# WikiAudio.net
KiCad netlist of a schematic drawn in Altium Designer
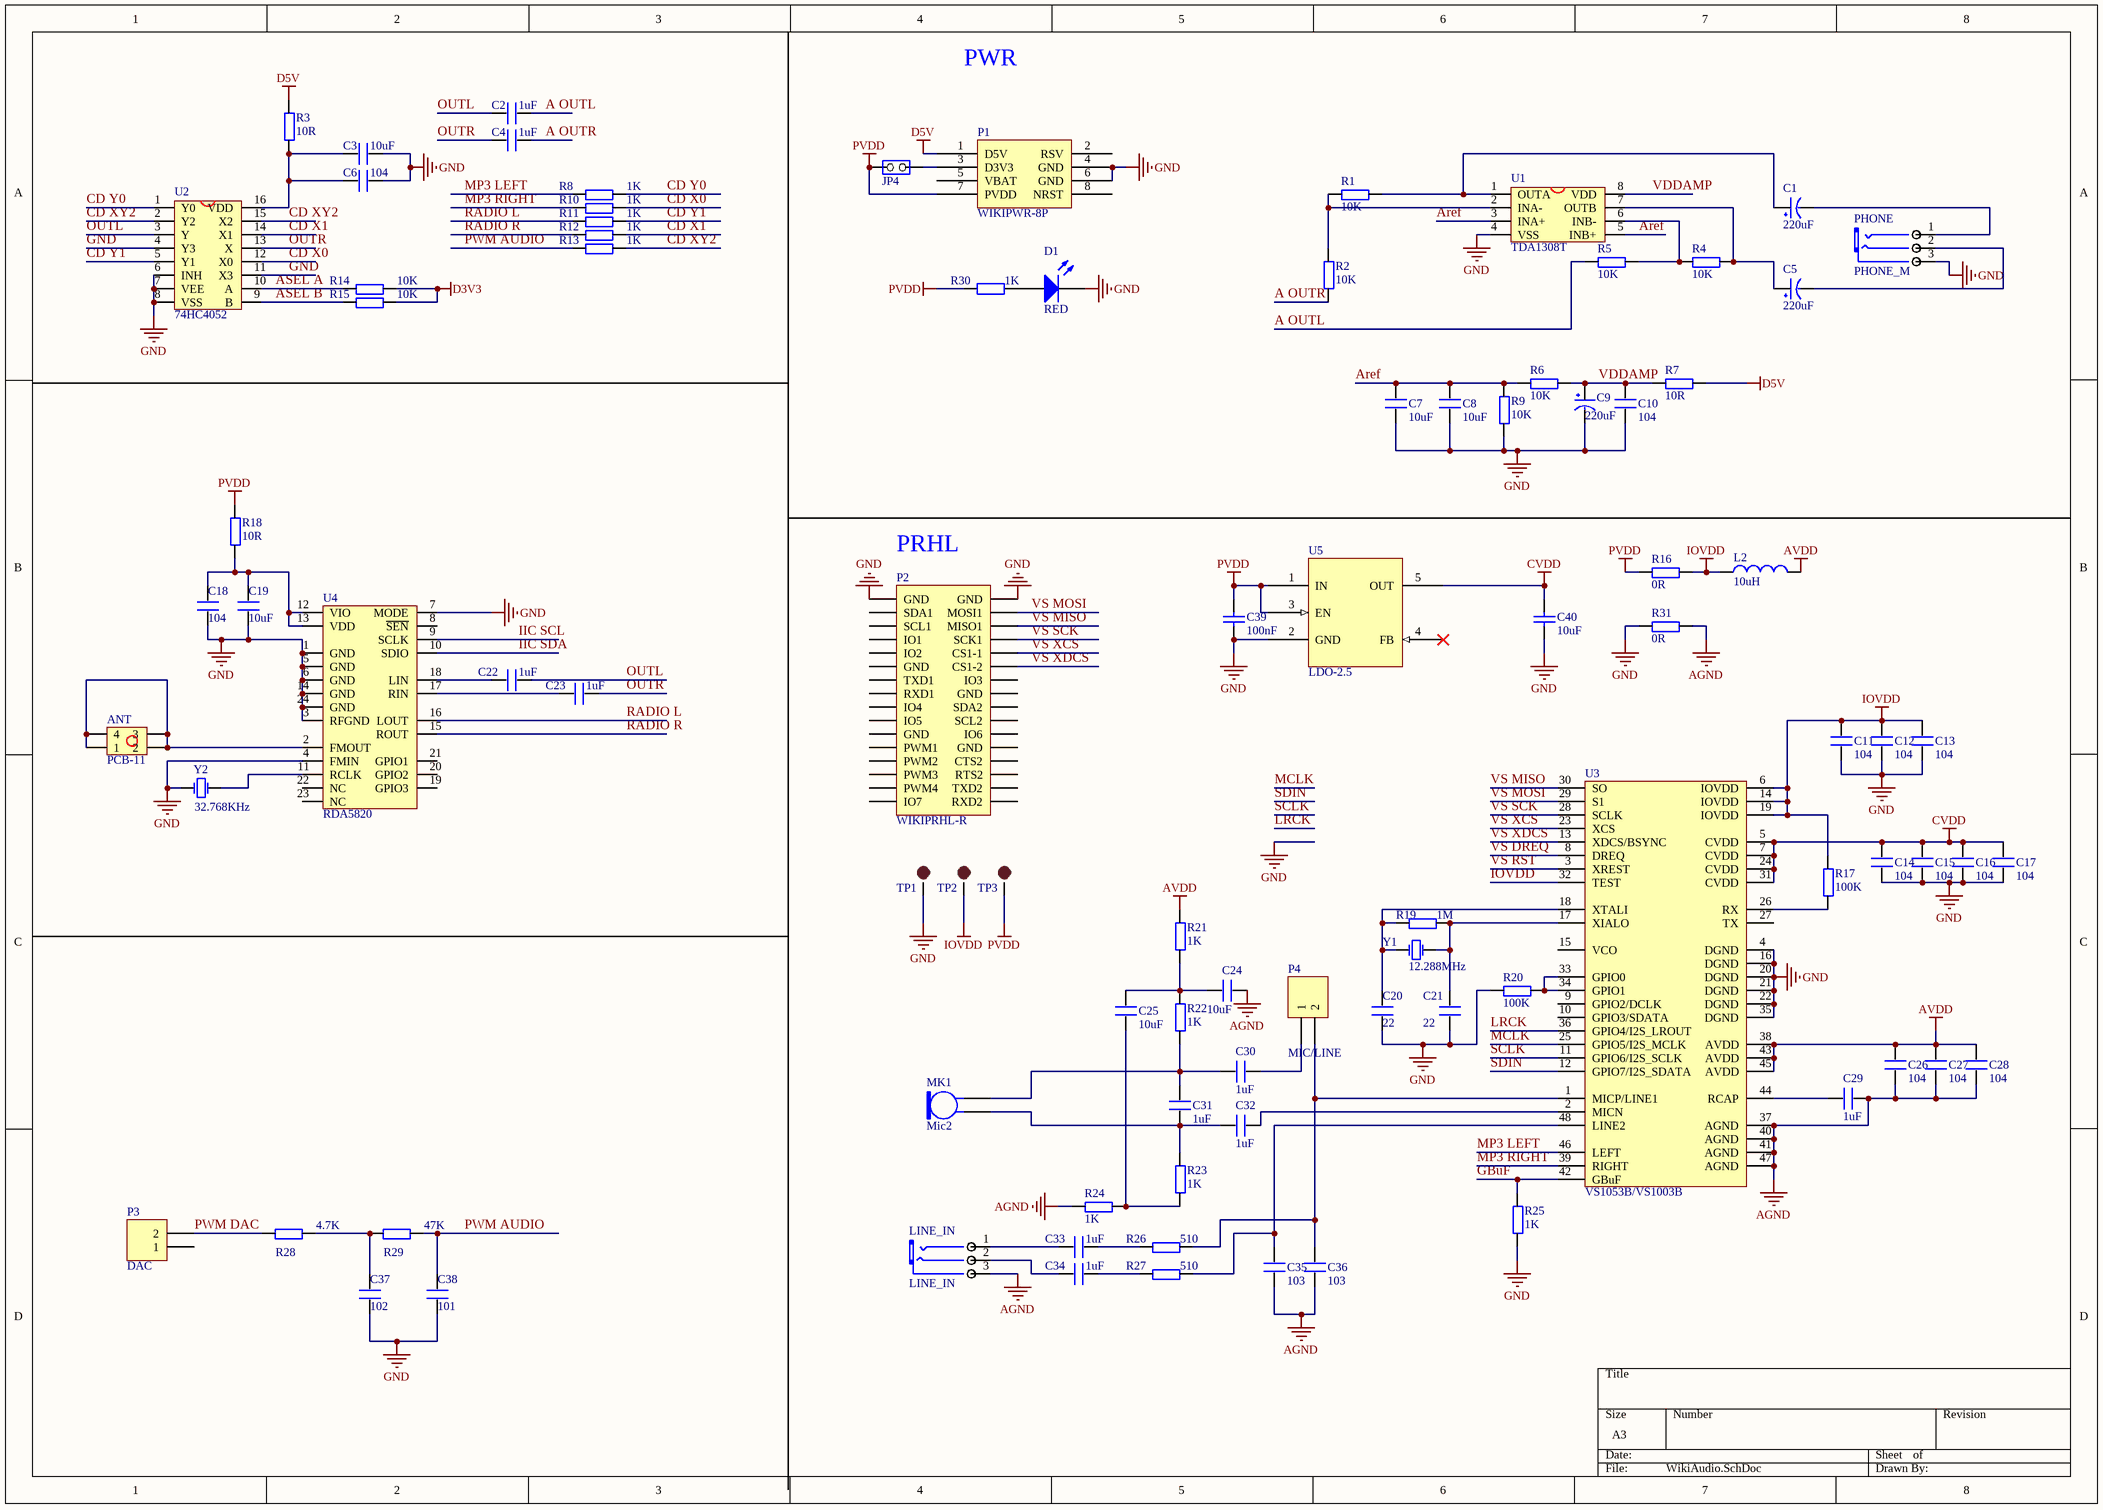
[diagram p0: WikiAudio.SchDoc]

(export (version "E")
  (design (tool "Eeschema 10.0.6"))
  (components
    (comp (ref "ANT")
      (value "PCB-11")
      (footprint "PCB-11")
      (description "PCB接线端子")
      (libsource (lib "战舰STM32开发板底板封装库") (part "PCB-11"))
    )
    (comp (ref "C1") (value "220uF") (footprint "CC6.56.5") (libsource (lib "战舰STM32开发板底板封装库") (part "CAP")))
    (comp (ref "C2") (value "1uF") (footprint "0603P") (libsource (lib "战舰STM32开发板底板封装库") (part "C")))
    (comp (ref "C3") (value "10uF") (footprint "0603P") (libsource (lib "战舰STM32开发板底板封装库") (part "C")))
    (comp (ref "C4") (value "1uF") (footprint "0603P") (libsource (lib "战舰STM32开发板底板封装库") (part "C")))
    (comp (ref "C5") (value "220uF") (footprint "CC6.56.5") (libsource (lib "战舰STM32开发板底板封装库") (part "CAP")))
    (comp (ref "C6") (value "104") (footprint "0603P") (libsource (lib "战舰STM32开发板底板封装库") (part "C")))
    (comp (ref "C7") (value "10uF") (footprint "0603P") (libsource (lib "战舰STM32开发板底板封装库") (part "C")))
    (comp (ref "C8") (value "10uF") (footprint "0603P") (libsource (lib "战舰STM32开发板底板封装库") (part "C")))
    (comp (ref "C9") (value "220uF") (footprint "CC6.56.5") (libsource (lib "") (part "CAP_1")))
    (comp (ref "C10") (value "104") (footprint "0603P") (libsource (lib "战舰STM32开发板底板封装库") (part "C")))
    (comp (ref "C11") (value "104") (footprint "0603P") (libsource (lib "战舰STM32开发板底板封装库") (part "C")))
    (comp (ref "C12") (value "104") (footprint "0603P") (libsource (lib "战舰STM32开发板底板封装库") (part "C")))
    (comp (ref "C13") (value "104") (footprint "0603P") (libsource (lib "战舰STM32开发板底板封装库") (part "C")))
    (comp (ref "C14") (value "104") (footprint "0603P") (libsource (lib "战舰STM32开发板底板封装库") (part "C")))
    (comp (ref "C15") (value "104") (footprint "0603P") (libsource (lib "战舰STM32开发板底板封装库") (part "C")))
    (comp (ref "C16") (value "104") (footprint "0603P") (libsource (lib "战舰STM32开发板底板封装库") (part "C")))
    (comp (ref "C17") (value "104") (footprint "0603P") (libsource (lib "战舰STM32开发板底板封装库") (part "C")))
    (comp (ref "C18") (value "104") (footprint "0603P") (libsource (lib "战舰STM32开发板底板封装库") (part "C")))
    (comp (ref "C19") (value "10uF") (footprint "0603P") (libsource (lib "战舰STM32开发板底板封装库") (part "C")))
    (comp (ref "C20") (value "22") (footprint "0603P") (libsource (lib "战舰STM32开发板底板封装库") (part "C")))
    (comp (ref "C21") (value "22") (footprint "0603P") (libsource (lib "战舰STM32开发板底板封装库") (part "C")))
    (comp (ref "C22") (value "1uF") (footprint "0603P") (libsource (lib "战舰STM32开发板底板封装库") (part "C")))
    (comp (ref "C23") (value "1uF") (footprint "0603P") (libsource (lib "战舰STM32开发板底板封装库") (part "C")))
    (comp (ref "C24") (value "10uF") (footprint "0603P") (libsource (lib "战舰STM32开发板底板封装库") (part "C")))
    (comp (ref "C25") (value "10uF") (footprint "0603P") (libsource (lib "战舰STM32开发板底板封装库") (part "C")))
    (comp (ref "C26") (value "104") (footprint "0603P") (libsource (lib "战舰STM32开发板底板封装库") (part "C")))
    (comp (ref "C27") (value "104") (footprint "0603P") (libsource (lib "战舰STM32开发板底板封装库") (part "C")))
    (comp (ref "C28") (value "104") (footprint "0603P") (libsource (lib "战舰STM32开发板底板封装库") (part "C")))
    (comp (ref "C29") (value "1uF") (footprint "0603P") (libsource (lib "战舰STM32开发板底板封装库") (part "C")))
    (comp (ref "C30") (value "1uF") (footprint "0603P") (libsource (lib "战舰STM32开发板底板封装库") (part "C")))
    (comp (ref "C31") (value "1uF") (footprint "0603P") (libsource (lib "战舰STM32开发板底板封装库") (part "C")))
    (comp (ref "C32") (value "1uF") (footprint "0603P") (libsource (lib "战舰STM32开发板底板封装库") (part "C")))
    (comp (ref "C33") (value "1uF") (footprint "0603P") (libsource (lib "战舰STM32开发板底板封装库") (part "C")))
    (comp (ref "C34") (value "1uF") (footprint "0603P") (libsource (lib "战舰STM32开发板底板封装库") (part "C")))
    (comp (ref "C35") (value "103") (footprint "0603P") (libsource (lib "战舰STM32开发板底板封装库") (part "C")))
    (comp (ref "C36") (value "103") (footprint "0603P") (libsource (lib "战舰STM32开发板底板封装库") (part "C")))
    (comp (ref "C37") (value "102") (footprint "0603P") (libsource (lib "战舰STM32开发板底板封装库") (part "C")))
    (comp (ref "C38") (value "101") (footprint "0603P") (libsource (lib "战舰STM32开发板底板封装库") (part "C")))
    (comp (ref "C39")
      (value "100nF")
      (footprint "C0603L")
      (description "Capacitor")
      (fields (field (name "PUBLISHER") "Altium Limited"))
      (libsource (lib "Miscellaneous Devices") (part "Cap"))
    )
    (comp (ref "C40")
      (value "10uF")
      (footprint "C0805")
      (description "Capacitor")
      (fields (field (name "PUBLISHER") "Altium Limited"))
      (libsource (lib "Miscellaneous Devices") (part "Cap"))
    )
    (comp (ref "D1")
      (value "RED")
      (footprint "0603pn")
      (description "Typical INFRARED GaAs LED")
      (fields (field (name "PUBLISHER") "Altium Limited"))
      (libsource (lib "Miscellaneous Devices") (part "LED0"))
    )
    (comp (ref "JP4")
      (value "Jumper2-2")
      (footprint "JP2_SMD")
      (description "Jumper2")
      (libsource (lib "Misc") (part "Jumper2-2"))
    )
    (comp (ref "L2")
      (value "10uH")
      (footprint "0805")
      (description "Inductor")
      (fields (field (name "PUBLISHER") "Altium Limited"))
      (libsource (lib "Misc") (part "Inductor"))
    )
    (comp (ref "LINE_IN")
      (value "LINE_IN")
      (footprint "PHONE_ST")
      (libsource (lib "战舰STM32开发板底板封装库") (part "PHONE_M"))
    )
    (comp (ref "MK1")
      (value "Mic2")
      (footprint "Mic-6050")
      (description "Microphone")
      (fields (field (name "PUBLISHER") "Altium Limited"))
      (libsource (lib "Misc") (part "Mic2"))
    )
    (comp (ref "P1")
      (value "WIKIPWR-8P")
      (footprint "WIKIPWR-8P")
      (description "PWR HDR")
      (libsource (lib "Connector") (part "WIKIPWR-8P"))
    )
    (comp (ref "P2")
      (value "WIKIPRHL-R")
      (footprint "WIKIPRHL-R")
      (description "Header, 16-Pin, Dual row")
      (fields (field (name "PUBLISHER") "Altium Limited"))
      (libsource (lib "Connector") (part "WIKIPRHL-R"))
    )
    (comp (ref "P3")
      (value "DAC")
      (footprint "HDR1X2")
      (description "Header, 2-Pin")
      (fields (field (name "PUBLISHER") "Altium Limited"))
      (libsource (lib "战舰STM32开发板底板封装库") (part "Header 2"))
    )
    (comp (ref "P4")
      (value "MIC/LINE")
      (footprint "HDR1X2/2.00MM")
      (description "Header, 2-Pin")
      (fields (field (name "PUBLISHER") "Altium Limited"))
      (libsource (lib "altium-import") (part "root_1_Header 2_"))
    )
    (comp (ref "PHONE")
      (value "PHONE_M")
      (footprint "PHONE_ST")
      (libsource (lib "战舰STM32开发板底板封装库") (part "PHONE_M"))
    )
    (comp (ref "R1") (value "10K") (footprint "0603P") (libsource (lib "战舰STM32开发板底板封装库") (part "R")))
    (comp (ref "R2") (value "10K") (footprint "0603P") (libsource (lib "战舰STM32开发板底板封装库") (part "R")))
    (comp (ref "R3") (value "10R") (footprint "0603P") (libsource (lib "战舰STM32开发板底板封装库") (part "R")))
    (comp (ref "R4") (value "10K") (footprint "0603P") (libsource (lib "战舰STM32开发板底板封装库") (part "R")))
    (comp (ref "R5") (value "10K") (footprint "0603P") (libsource (lib "战舰STM32开发板底板封装库") (part "R")))
    (comp (ref "R6") (value "10K") (footprint "0603P") (libsource (lib "战舰STM32开发板底板封装库") (part "R")))
    (comp (ref "R7") (value "10R") (footprint "0603P") (libsource (lib "战舰STM32开发板底板封装库") (part "R")))
    (comp (ref "R8") (value "1K") (footprint "0603P") (libsource (lib "战舰STM32开发板底板封装库") (part "R")))
    (comp (ref "R9") (value "10K") (footprint "0603P") (libsource (lib "战舰STM32开发板底板封装库") (part "R")))
    (comp (ref "R10") (value "1K") (footprint "0603P") (libsource (lib "战舰STM32开发板底板封装库") (part "R")))
    (comp (ref "R11") (value "1K") (footprint "0603P") (libsource (lib "战舰STM32开发板底板封装库") (part "R")))
    (comp (ref "R12") (value "1K") (footprint "0603P") (libsource (lib "战舰STM32开发板底板封装库") (part "R")))
    (comp (ref "R13") (value "1K") (footprint "0603P") (libsource (lib "战舰STM32开发板底板封装库") (part "R")))
    (comp (ref "R14") (value "10K") (footprint "0603P") (libsource (lib "战舰STM32开发板底板封装库") (part "R")))
    (comp (ref "R15") (value "10K") (footprint "0603P") (libsource (lib "战舰STM32开发板底板封装库") (part "R")))
    (comp (ref "R16")
      (value "0R")
      (footprint "0603P")
      (libsource (lib "altium-import") (part "root_0_mirrored_R_"))
    )
    (comp (ref "R17") (value "100K") (footprint "0603P") (libsource (lib "战舰STM32开发板底板封装库") (part "R")))
    (comp (ref "R18") (value "10R") (footprint "0603P") (libsource (lib "战舰STM32开发板底板封装库") (part "R")))
    (comp (ref "R19") (value "1M") (footprint "0603P") (libsource (lib "战舰STM32开发板底板封装库") (part "R")))
    (comp (ref "R20") (value "100K") (footprint "0603P") (libsource (lib "战舰STM32开发板底板封装库") (part "R")))
    (comp (ref "R21") (value "1K") (footprint "0603P") (libsource (lib "战舰STM32开发板底板封装库") (part "R")))
    (comp (ref "R22") (value "1K") (footprint "0603P") (libsource (lib "战舰STM32开发板底板封装库") (part "R")))
    (comp (ref "R23") (value "1K") (footprint "0603P") (libsource (lib "战舰STM32开发板底板封装库") (part "R")))
    (comp (ref "R24") (value "1K") (footprint "0603P") (libsource (lib "战舰STM32开发板底板封装库") (part "R")))
    (comp (ref "R25") (value "1K") (footprint "0603P") (libsource (lib "战舰STM32开发板底板封装库") (part "R")))
    (comp (ref "R26") (value "510") (footprint "0603P") (libsource (lib "战舰STM32开发板底板封装库") (part "R")))
    (comp (ref "R27") (value "510") (footprint "0603P") (libsource (lib "战舰STM32开发板底板封装库") (part "R")))
    (comp (ref "R28") (value "4.7K") (footprint "0603P") (libsource (lib "战舰STM32开发板底板封装库") (part "R")))
    (comp (ref "R29") (value "47K") (footprint "0603P") (libsource (lib "战舰STM32开发板底板封装库") (part "R")))
    (comp (ref "R30")
      (value "1K")
      (footprint "0603M")
      (description "Resistor")
      (fields (field (name "PUBLISHER") "Altium Limited"))
      (libsource (lib "Miscellaneous Devices") (part "Res2"))
    )
    (comp (ref "R31")
      (value "0R")
      (footprint "0603P")
      (libsource (lib "altium-import") (part "root_0_mirrored_R_"))
    )
    (comp (ref "TP1")
      (value "TEST POINT")
      (footprint "TP-1.5")
      (description "测试点")
      (libsource (lib "战舰STM32开发板底板封装库") (part "TEST-POINT"))
    )
    (comp (ref "TP2")
      (value "TEST POINT")
      (footprint "TP-1.5")
      (description "测试点")
      (libsource (lib "战舰STM32开发板底板封装库") (part "TEST-POINT"))
    )
    (comp (ref "TP3")
      (value "TEST POINT")
      (footprint "TP-1.5")
      (description "测试点")
      (libsource (lib "战舰STM32开发板底板封装库") (part "TEST-POINT"))
    )
    (comp (ref "U1")
      (value "TDA1308T")
      (footprint "SOP-8")
      (libsource (lib "战舰STM32开发板底板封装库") (part "TDA1308"))
    )
    (comp (ref "U2")
      (value "74HC4052")
      (footprint "SOP16M")
      (libsource (lib "战舰STM32开发板底板封装库") (part "CD4052"))
    )
    (comp (ref "U3")
      (value "VS1053B/VS1003B")
      (footprint "mTQFP48")
      (libsource (lib "altium-import") (part "root_0_VS1053_"))
    )
    (comp (ref "U4")
      (value "RDA5820")
      (footprint "QFN24")
      (libsource (lib "战舰STM32开发板底板封装库") (part "RDA5820"))
    )
    (comp (ref "U5")
      (value "LDO-2.5")
      (footprint "SOT23-5")
      (description "General LDO SOT23-5")
      (libsource (lib "Power") (part "LDO-SOT23-5"))
    )
    (comp (ref "Y1")
      (value "12.288MHz")
      (footprint "XTAL_US")
      (description "Crystal Oscillator")
      (fields (field (name "PUBLISHER") "Altium Limited"))
      (libsource (lib "战舰STM32开发板底板封装库") (part "XTAL_2"))
    )
    (comp (ref "Y2")
      (value "32.768KHz")
      (footprint "XTAL32")
      (description "32.768K")
      (fields (field (name "PUBLISHER") "Altium Limited"))
      (libsource (lib "战舰STM32开发板底板封装库") (part "XTAL_3"))
    )
  )
  (nets
    (net (code "1") (name "/A OUTL") (class "Default")
      (node (ref "C2") (pin "2") (pintype "passive"))
      (node (ref "R5") (pin "1") (pintype "passive"))
    )
    (net (code "2") (name "/A OUTR") (class "Default")
      (node (ref "C4") (pin "2") (pintype "passive"))
      (node (ref "R2") (pin "1") (pintype "passive"))
    )
    (net (code "3") (name "/ASEL A") (class "Default")
      (node (ref "R14") (pin "1") (pintype "passive"))
      (node (ref "U2") (pin "10") (pinfunction "A_10") (pintype "passive"))
    )
    (net (code "4") (name "/ASEL B") (class "Default")
      (node (ref "R15") (pin "1") (pintype "passive"))
      (node (ref "U2") (pin "9") (pinfunction "B_9") (pintype "passive"))
    )
    (net (code "5") (name "/Aref") (class "Default")
      (node (ref "C7") (pin "2") (pintype "passive"))
      (node (ref "C8") (pin "2") (pintype "passive"))
      (node (ref "R6") (pin "1") (pintype "passive"))
      (node (ref "R9") (pin "2") (pintype "passive"))
      (node (ref "U1") (pin "3") (pinfunction "INA+_3") (pintype "passive"))
      (node (ref "U1") (pin "5") (pinfunction "INB+_5") (pintype "passive"))
    )
    (net (code "6") (name "/CD X0") (class "Default")
      (node (ref "R10") (pin "2") (pintype "passive"))
      (node (ref "U2") (pin "12") (pinfunction "X0_12") (pintype "passive"))
    )
    (net (code "7") (name "/CD X1") (class "Default")
      (node (ref "R12") (pin "2") (pintype "passive"))
      (node (ref "U2") (pin "14") (pinfunction "X1_14") (pintype "passive"))
    )
    (net (code "8") (name "/CD XY2") (class "Default")
      (node (ref "R13") (pin "2") (pintype "passive"))
      (node (ref "U2") (pin "15") (pinfunction "X2_15") (pintype "passive"))
      (node (ref "U2") (pin "2") (pinfunction "Y2_2") (pintype "passive"))
    )
    (net (code "9") (name "/CD Y0") (class "Default")
      (node (ref "R8") (pin "2") (pintype "passive"))
      (node (ref "U2") (pin "1") (pinfunction "Y0_1") (pintype "passive"))
    )
    (net (code "10") (name "/CD Y1") (class "Default")
      (node (ref "R11") (pin "2") (pintype "passive"))
      (node (ref "U2") (pin "5") (pinfunction "Y1_5") (pintype "passive"))
    )
    (net (code "11") (name "/GBuF") (class "Default")
      (node (ref "R25") (pin "2") (pintype "passive"))
      (node (ref "U3") (pin "42") (pinfunction "GBuF_42") (pintype "passive"))
    )
    (net (code "12") (name "/IIC SCL") (class "Default")
      (node (ref "U4") (pin "9") (pinfunction "SCLK_9") (pintype "passive"))
    )
    (net (code "13") (name "/IIC SDA") (class "Default")
      (node (ref "U4") (pin "10") (pinfunction "SDIO_10") (pintype "passive"))
    )
    (net (code "14") (name "/LRCK") (class "Default")
      (node (ref "U3") (pin "36") (pinfunction "GPIO4/I2S_LROUT_36") (pintype "passive"))
    )
    (net (code "15") (name "/MCLK") (class "Default")
      (node (ref "U3") (pin "25") (pinfunction "GPIO5/I2S_MCLK_25") (pintype "passive"))
    )
    (net (code "16") (name "/MP3 LEFT") (class "Default")
      (node (ref "R8") (pin "1") (pintype "passive"))
      (node (ref "U3") (pin "46") (pinfunction "LEFT_46") (pintype "passive"))
    )
    (net (code "17") (name "/MP3 RIGHT") (class "Default")
      (node (ref "R10") (pin "1") (pintype "passive"))
      (node (ref "U3") (pin "39") (pinfunction "RIGHT_39") (pintype "passive"))
    )
    (net (code "18") (name "/OUTL") (class "Default")
      (node (ref "C2") (pin "1") (pintype "passive"))
      (node (ref "C22") (pin "1") (pintype "passive"))
      (node (ref "U2") (pin "3") (pinfunction "Y_3") (pintype "passive"))
    )
    (net (code "19") (name "/OUTR") (class "Default")
      (node (ref "C23") (pin "1") (pintype "passive"))
      (node (ref "C4") (pin "1") (pintype "passive"))
      (node (ref "U2") (pin "13") (pinfunction "X_13") (pintype "passive"))
    )
    (net (code "20") (name "/PWM AUDIO") (class "Default")
      (node (ref "C38") (pin "2") (pintype "passive"))
      (node (ref "R13") (pin "1") (pintype "passive"))
      (node (ref "R29") (pin "2") (pintype "passive"))
    )
    (net (code "21") (name "/PWM DAC") (class "Default")
      (node (ref "P3") (pin "2") (pinfunction "2_2") (pintype "passive"))
      (node (ref "R28") (pin "1") (pintype "passive"))
    )
    (net (code "22") (name "/RADIO L") (class "Default")
      (node (ref "R11") (pin "1") (pintype "passive"))
      (node (ref "U4") (pin "16") (pinfunction "LOUT_16") (pintype "passive"))
    )
    (net (code "23") (name "/RADIO R") (class "Default")
      (node (ref "R12") (pin "1") (pintype "passive"))
      (node (ref "U4") (pin "15") (pinfunction "ROUT_15") (pintype "passive"))
    )
    (net (code "24") (name "/SCLK") (class "Default")
      (node (ref "U3") (pin "11") (pinfunction "GPIO6/I2S_SCLK_11") (pintype "passive"))
    )
    (net (code "25") (name "/SDIN") (class "Default")
      (node (ref "U3") (pin "12") (pinfunction "GPIO7/I2S_SDATA_12") (pintype "passive"))
    )
    (net (code "26") (name "/VDDAMP") (class "Default")
      (node (ref "C10") (pin "2") (pintype "passive"))
      (node (ref "C9") (pin "1") (pinfunction "VCC_1") (pintype "passive"))
      (node (ref "R6") (pin "2") (pintype "passive"))
      (node (ref "R7") (pin "1") (pintype "passive"))
      (node (ref "U1") (pin "8") (pinfunction "VDD_8") (pintype "passive"))
    )
    (net (code "27") (name "/VS DREQ") (class "Default")
      (node (ref "U3") (pin "8") (pinfunction "DREQ_8") (pintype "passive"))
    )
    (net (code "28") (name "/VS MISO") (class "Default")
      (node (ref "P2") (pin "6") (pinfunction "MISO1_6") (pintype "passive"))
      (node (ref "U3") (pin "30") (pinfunction "SO_30") (pintype "passive"))
    )
    (net (code "29") (name "/VS MOSI") (class "Default")
      (node (ref "P2") (pin "4") (pinfunction "MOSI1_4") (pintype "passive"))
      (node (ref "U3") (pin "29") (pinfunction "S1_29") (pintype "passive"))
    )
    (net (code "30") (name "/VS RST") (class "Default")
      (node (ref "U3") (pin "3") (pinfunction "XREST_3") (pintype "passive"))
    )
    (net (code "31") (name "/VS SCK") (class "Default")
      (node (ref "P2") (pin "8") (pinfunction "SCK1_8") (pintype "passive"))
      (node (ref "U3") (pin "28") (pinfunction "SCLK_28") (pintype "passive"))
    )
    (net (code "32") (name "/VS XCS") (class "Default")
      (node (ref "P2") (pin "10") (pinfunction "CS1-1_10") (pintype "passive"))
      (node (ref "U3") (pin "23") (pinfunction "XCS_23") (pintype "passive"))
    )
    (net (code "33") (name "/VS XDCS") (class "Default")
      (node (ref "P2") (pin "12") (pinfunction "CS1-2_12") (pintype "passive"))
      (node (ref "U3") (pin "13") (pinfunction "XDCS/BSYNC_13") (pintype "passive"))
    )
    (net (code "34") (name "AGND") (class "Default")
      (node (ref "C24") (pin "1") (pintype "passive"))
      (node (ref "C26") (pin "1") (pintype "passive"))
      (node (ref "C27") (pin "1") (pintype "passive"))
      (node (ref "C28") (pin "1") (pintype "passive"))
      (node (ref "C29") (pin "2") (pintype "passive"))
      (node (ref "C35") (pin "1") (pintype "passive"))
      (node (ref "C36") (pin "1") (pintype "passive"))
      (node (ref "LINE_IN") (pin "3") (pinfunction "COM_3") (pintype "passive"))
      (node (ref "R24") (pin "1") (pintype "passive"))
      (node (ref "R31") (pin "1") (pintype "passive"))
      (node (ref "U3") (pin "37") (pinfunction "AGND_37") (pintype "passive"))
      (node (ref "U3") (pin "40") (pinfunction "AGND_40") (pintype "passive"))
      (node (ref "U3") (pin "41") (pinfunction "AGND_41") (pintype "passive"))
      (node (ref "U3") (pin "47") (pinfunction "AGND_47") (pintype "passive"))
    )
    (net (code "35") (name "AVDD") (class "Default")
      (node (ref "C26") (pin "2") (pintype "passive"))
      (node (ref "C27") (pin "2") (pintype "passive"))
      (node (ref "C28") (pin "2") (pintype "passive"))
      (node (ref "L2") (pin "2") (pinfunction "2_2") (pintype "passive"))
      (node (ref "R21") (pin "2") (pintype "passive"))
      (node (ref "U3") (pin "38") (pinfunction "AVDD_38") (pintype "passive"))
      (node (ref "U3") (pin "43") (pinfunction "AVDD_43") (pintype "passive"))
      (node (ref "U3") (pin "45") (pinfunction "AVDD_45") (pintype "passive"))
    )
    (net (code "36") (name "CVDD") (class "Default")
      (node (ref "C14") (pin "2") (pintype "passive"))
      (node (ref "C15") (pin "2") (pintype "passive"))
      (node (ref "C16") (pin "2") (pintype "passive"))
      (node (ref "C17") (pin "2") (pintype "passive"))
      (node (ref "C40") (pin "1") (pinfunction "1_1") (pintype "passive"))
      (node (ref "U3") (pin "24") (pinfunction "CVDD_24") (pintype "passive"))
      (node (ref "U3") (pin "31") (pinfunction "CVDD_31") (pintype "passive"))
      (node (ref "U3") (pin "5") (pinfunction "CVDD_5") (pintype "passive"))
      (node (ref "U3") (pin "7") (pinfunction "CVDD_7") (pintype "passive"))
      (node (ref "U5") (pin "5") (pinfunction "OUT_5") (pintype "power_in"))
    )
    (net (code "37") (name "D3V3") (class "Default")
      (node (ref "R14") (pin "2") (pintype "passive"))
      (node (ref "R15") (pin "2") (pintype "passive"))
    )
    (net (code "38") (name "D5V") (class "Default")
      (node (ref "P1") (pin "1") (pinfunction "D5V_1") (pintype "passive"))
      (node (ref "R3") (pin "2") (pintype "passive"))
      (node (ref "R7") (pin "2") (pintype "passive"))
    )
    (net (code "39") (name "GND") (class "Default")
      (node (ref "C10") (pin "1") (pintype "passive"))
      (node (ref "C11") (pin "1") (pintype "passive"))
      (node (ref "C12") (pin "1") (pintype "passive"))
      (node (ref "C13") (pin "1") (pintype "passive"))
      (node (ref "C14") (pin "1") (pintype "passive"))
      (node (ref "C15") (pin "1") (pintype "passive"))
      (node (ref "C16") (pin "1") (pintype "passive"))
      (node (ref "C17") (pin "1") (pintype "passive"))
      (node (ref "C18") (pin "1") (pintype "passive"))
      (node (ref "C19") (pin "1") (pintype "passive"))
      (node (ref "C20") (pin "1") (pintype "passive"))
      (node (ref "C21") (pin "1") (pintype "passive"))
      (node (ref "C3") (pin "2") (pintype "passive"))
      (node (ref "C37") (pin "1") (pintype "passive"))
      (node (ref "C38") (pin "1") (pintype "passive"))
      (node (ref "C39") (pin "2") (pinfunction "2_2") (pintype "passive"))
      (node (ref "C40") (pin "2") (pinfunction "2_2") (pintype "passive"))
      (node (ref "C6") (pin "2") (pintype "passive"))
      (node (ref "C7") (pin "1") (pintype "passive"))
      (node (ref "C8") (pin "1") (pintype "passive"))
      (node (ref "C9") (pin "2") (pinfunction "GND_2") (pintype "passive"))
      (node (ref "D1") (pin "2") (pinfunction "K_2") (pintype "passive"))
      (node (ref "P1") (pin "4") (pinfunction "GND_4") (pintype "passive"))
      (node (ref "P1") (pin "6") (pinfunction "GND_6") (pintype "passive"))
      (node (ref "P2") (pin "1") (pinfunction "GND_1") (pintype "passive"))
      (node (ref "P2") (pin "2") (pinfunction "GND_2") (pintype "passive"))
      (node (ref "PHONE") (pin "3") (pinfunction "COM_3") (pintype "passive"))
      (node (ref "R20") (pin "1") (pintype "passive"))
      (node (ref "R25") (pin "1") (pintype "passive"))
      (node (ref "R31") (pin "2") (pintype "passive"))
      (node (ref "R9") (pin "1") (pintype "passive"))
      (node (ref "TP1") (pin "1") (pinfunction "1_1") (pintype "passive"))
      (node (ref "U1") (pin "4") (pinfunction "VSS_4") (pintype "passive"))
      (node (ref "U2") (pin "11") (pinfunction "X3_11") (pintype "passive"))
      (node (ref "U2") (pin "4") (pinfunction "Y3_4") (pintype "passive"))
      (node (ref "U2") (pin "6") (pinfunction "INH_6") (pintype "passive"))
      (node (ref "U2") (pin "7") (pinfunction "VEE_7") (pintype "passive"))
      (node (ref "U2") (pin "8") (pinfunction "VSS_8") (pintype "passive"))
      (node (ref "U3") (pin "16") (pinfunction "DGND_16") (pintype "passive"))
      (node (ref "U3") (pin "20") (pinfunction "DGND_20") (pintype "passive"))
      (node (ref "U3") (pin "21") (pinfunction "DGND_21") (pintype "passive"))
      (node (ref "U3") (pin "22") (pinfunction "DGND_22") (pintype "passive"))
      (node (ref "U3") (pin "35") (pinfunction "DGND_35") (pintype "passive"))
      (node (ref "U3") (pin "4") (pinfunction "DGND_4") (pintype "passive"))
      (node (ref "U4") (pin "1") (pinfunction "GND_1") (pintype "passive"))
      (node (ref "U4") (pin "14") (pinfunction "GND_14") (pintype "passive"))
      (node (ref "U4") (pin "24") (pinfunction "GND_24") (pintype "passive"))
      (node (ref "U4") (pin "3") (pinfunction "RFGND_3") (pintype "passive"))
      (node (ref "U4") (pin "4") (pinfunction "FMIN_4") (pintype "passive"))
      (node (ref "U4") (pin "5") (pinfunction "GND_5") (pintype "passive"))
      (node (ref "U4") (pin "6") (pinfunction "GND_6") (pintype "passive"))
      (node (ref "U4") (pin "7") (pinfunction "MODE_7") (pintype "passive"))
      (node (ref "U5") (pin "2") (pinfunction "GND_2") (pintype "power_in"))
      (node (ref "Y2") (pin "1") (pinfunction "OSC1_1") (pintype "passive"))
    )
    (net (code "40") (name "IOVDD") (class "Default")
      (node (ref "C11") (pin "2") (pintype "passive"))
      (node (ref "C12") (pin "2") (pintype "passive"))
      (node (ref "C13") (pin "2") (pintype "passive"))
      (node (ref "L2") (pin "1") (pinfunction "1_1") (pintype "passive"))
      (node (ref "R16") (pin "1") (pintype "passive"))
      (node (ref "R17") (pin "2") (pintype "passive"))
      (node (ref "TP2") (pin "1") (pinfunction "1_1") (pintype "passive"))
      (node (ref "U3") (pin "14") (pinfunction "IOVDD_14") (pintype "passive"))
      (node (ref "U3") (pin "19") (pinfunction "IOVDD_19") (pintype "passive"))
      (node (ref "U3") (pin "32") (pinfunction "TEST_32") (pintype "passive"))
      (node (ref "U3") (pin "6") (pinfunction "IOVDD_6") (pintype "passive"))
    )
    (net (code "41") (name "Net-(C1-GND)") (class "Default")
      (node (ref "C1") (pin "2") (pinfunction "GND_2") (pintype "passive"))
      (node (ref "PHONE") (pin "1") (pinfunction "CHL_1") (pintype "passive"))
    )
    (net (code "42") (name "Net-(C1-VCC)") (class "Default")
      (node (ref "C1") (pin "1") (pinfunction "VCC_1") (pintype "passive"))
      (node (ref "R1") (pin "2") (pintype "passive"))
      (node (ref "U1") (pin "1") (pinfunction "OUTA_1") (pintype "passive"))
    )
    (net (code "43") (name "Net-(C5-GND)") (class "Default")
      (node (ref "C5") (pin "2") (pinfunction "GND_2") (pintype "passive"))
      (node (ref "PHONE") (pin "2") (pinfunction "CHR_2") (pintype "passive"))
    )
    (net (code "44") (name "Net-(C5-VCC)") (class "Default")
      (node (ref "C5") (pin "1") (pinfunction "VCC_1") (pintype "passive"))
      (node (ref "R4") (pin "2") (pintype "passive"))
      (node (ref "U1") (pin "7") (pinfunction "OUTB_7") (pintype "passive"))
    )
    (net (code "45") (name "Net-(C24-Pad2)") (class "Default")
      (node (ref "C24") (pin "2") (pintype "passive"))
      (node (ref "C25") (pin "2") (pintype "passive"))
      (node (ref "R21") (pin "1") (pintype "passive"))
      (node (ref "R22") (pin "2") (pintype "passive"))
    )
    (net (code "46") (name "Net-(C25-Pad1)") (class "Default")
      (node (ref "C25") (pin "1") (pintype "passive"))
      (node (ref "R23") (pin "1") (pintype "passive"))
      (node (ref "R24") (pin "2") (pintype "passive"))
    )
    (net (code "47") (name "Net-(C30-Pad1)") (class "Default")
      (node (ref "C30") (pin "1") (pintype "passive"))
      (node (ref "C31") (pin "2") (pintype "passive"))
      (node (ref "MK1") (pin "2") (pinfunction "2_2") (pintype "passive"))
      (node (ref "R22") (pin "1") (pintype "passive"))
    )
    (net (code "48") (name "Net-(C30-Pad2)") (class "Default")
      (node (ref "C30") (pin "2") (pintype "passive"))
      (node (ref "P4") (pin "1") (pinfunction "1_1") (pintype "passive"))
    )
    (net (code "49") (name "Net-(C31-Pad1)") (class "Default")
      (node (ref "C31") (pin "1") (pintype "passive"))
      (node (ref "C32") (pin "1") (pintype "passive"))
      (node (ref "MK1") (pin "1") (pinfunction "1_1") (pintype "passive"))
      (node (ref "R23") (pin "2") (pintype "passive"))
    )
    (net (code "50") (name "Net-(C33-Pad2)") (class "Default")
      (node (ref "C33") (pin "2") (pintype "passive"))
      (node (ref "R26") (pin "1") (pintype "passive"))
    )
    (net (code "51") (name "Net-(C34-Pad2)") (class "Default")
      (node (ref "C34") (pin "2") (pintype "passive"))
      (node (ref "R27") (pin "1") (pintype "passive"))
    )
    (net (code "52") (name "Net-(C37-Pad2)") (class "Default")
      (node (ref "C37") (pin "2") (pintype "passive"))
      (node (ref "R28") (pin "2") (pintype "passive"))
      (node (ref "R29") (pin "1") (pintype "passive"))
    )
    (net (code "53") (name "Net-(D1-A)") (class "Default")
      (node (ref "D1") (pin "1") (pinfunction "A_1") (pintype "passive"))
      (node (ref "R30") (pin "1") (pinfunction "1_1") (pintype "passive"))
    )
    (net (code "54") (name "Net-(JP4-COMMON)") (class "Default")
      (node (ref "JP4") (pin "1") (pinfunction "COMMON_1") (pintype "passive"))
      (node (ref "P1") (pin "3") (pinfunction "D3V3_3") (pintype "passive"))
    )
    (net (code "55") (name "Net-(LINE_IN-CHL)") (class "Default")
      (node (ref "C33") (pin "1") (pintype "passive"))
      (node (ref "LINE_IN") (pin "1") (pinfunction "CHL_1") (pintype "passive"))
    )
    (net (code "56") (name "Net-(LINE_IN-CHR)") (class "Default")
      (node (ref "C34") (pin "1") (pintype "passive"))
      (node (ref "LINE_IN") (pin "2") (pinfunction "CHR_2") (pintype "passive"))
    )
    (net (code "57") (name "Net-(U1-INA-)") (class "Default")
      (node (ref "R1") (pin "1") (pintype "passive"))
      (node (ref "R2") (pin "2") (pintype "passive"))
      (node (ref "U1") (pin "2") (pinfunction "INA-_2") (pintype "passive"))
    )
    (net (code "58") (name "Net-(U1-INB-)") (class "Default")
      (node (ref "R4") (pin "1") (pintype "passive"))
      (node (ref "R5") (pin "2") (pintype "passive"))
      (node (ref "U1") (pin "6") (pinfunction "INB-_6") (pintype "passive"))
    )
    (net (code "59") (name "Net-(U2-VDD)") (class "Default")
      (node (ref "C3") (pin "1") (pintype "passive"))
      (node (ref "C6") (pin "1") (pintype "passive"))
      (node (ref "R3") (pin "1") (pintype "passive"))
      (node (ref "U2") (pin "16") (pinfunction "VDD_16") (pintype "passive"))
    )
    (net (code "60") (name "Net-(U3-GPIO0)") (class "Default")
      (node (ref "R20") (pin "2") (pintype "passive"))
      (node (ref "U3") (pin "33") (pinfunction "GPIO0_33") (pintype "passive"))
      (node (ref "U3") (pin "34") (pinfunction "GPIO1_34") (pintype "passive"))
    )
    (net (code "61") (name "Net-(U3-LINE2)") (class "Default")
      (node (ref "C35") (pin "2") (pintype "passive"))
      (node (ref "R27") (pin "2") (pintype "passive"))
      (node (ref "U3") (pin "48") (pinfunction "LINE2_48") (pintype "passive"))
    )
    (net (code "62") (name "Net-(U3-MICN)") (class "Default")
      (node (ref "C32") (pin "2") (pintype "passive"))
      (node (ref "U3") (pin "2") (pinfunction "MICN_2") (pintype "passive"))
    )
    (net (code "63") (name "Net-(U3-MICP{slash}LINE1)") (class "Default")
      (node (ref "C36") (pin "2") (pintype "passive"))
      (node (ref "P4") (pin "2") (pinfunction "2_2") (pintype "passive"))
      (node (ref "R26") (pin "2") (pintype "passive"))
      (node (ref "U3") (pin "1") (pinfunction "MICP/LINE1_1") (pintype "passive"))
    )
    (net (code "64") (name "Net-(U3-RCAP)") (class "Default")
      (node (ref "C29") (pin "1") (pintype "passive"))
      (node (ref "U3") (pin "44") (pinfunction "RCAP_44") (pintype "passive"))
    )
    (net (code "65") (name "Net-(U3-RX)") (class "Default")
      (node (ref "R17") (pin "1") (pintype "passive"))
      (node (ref "U3") (pin "26") (pinfunction "RX_26") (pintype "passive"))
    )
    (net (code "66") (name "Net-(U3-XIALO)") (class "Default")
      (node (ref "C21") (pin "2") (pintype "passive"))
      (node (ref "R19") (pin "2") (pintype "passive"))
      (node (ref "U3") (pin "17") (pinfunction "XIALO_17") (pintype "passive"))
      (node (ref "Y1") (pin "2") (pinfunction "OSC2_2") (pintype "passive"))
    )
    (net (code "67") (name "Net-(U3-XTALI)") (class "Default")
      (node (ref "C20") (pin "2") (pintype "passive"))
      (node (ref "R19") (pin "1") (pintype "passive"))
      (node (ref "U3") (pin "18") (pinfunction "XTALI_18") (pintype "passive"))
      (node (ref "Y1") (pin "1") (pinfunction "OSC1_1") (pintype "passive"))
    )
    (net (code "68") (name "Net-(U4-FMOUT)") (class "Default")
      (node (ref "ANT") (pin "1") (pinfunction "1_1") (pintype "passive"))
      (node (ref "ANT") (pin "2") (pinfunction "2_2") (pintype "passive"))
      (node (ref "ANT") (pin "3") (pinfunction "3_3") (pintype "passive"))
      (node (ref "ANT") (pin "4") (pinfunction "4_4") (pintype "passive"))
      (node (ref "U4") (pin "2") (pinfunction "FMOUT_2") (pintype "passive"))
    )
    (net (code "69") (name "Net-(U4-LIN)") (class "Default")
      (node (ref "C22") (pin "2") (pintype "passive"))
      (node (ref "U4") (pin "18") (pinfunction "LIN_18") (pintype "passive"))
    )
    (net (code "70") (name "Net-(U4-RCLK)") (class "Default")
      (node (ref "U4") (pin "11") (pinfunction "RCLK_11") (pintype "passive"))
      (node (ref "Y2") (pin "2") (pinfunction "OSC2_2") (pintype "passive"))
    )
    (net (code "71") (name "Net-(U4-RIN)") (class "Default")
      (node (ref "C23") (pin "2") (pintype "passive"))
      (node (ref "U4") (pin "17") (pinfunction "RIN_17") (pintype "passive"))
    )
    (net (code "72") (name "Net-(U4-VDD)") (class "Default")
      (node (ref "C18") (pin "2") (pintype "passive"))
      (node (ref "C19") (pin "2") (pintype "passive"))
      (node (ref "R18") (pin "1") (pintype "passive"))
      (node (ref "U4") (pin "12") (pinfunction "VIO_12") (pintype "passive"))
      (node (ref "U4") (pin "13") (pinfunction "VDD_13") (pintype "passive"))
    )
    (net (code "73") (name "PVDD") (class "Default")
      (node (ref "C39") (pin "1") (pinfunction "1_1") (pintype "passive"))
      (node (ref "JP4") (pin "2") (pinfunction "NO_2") (pintype "passive"))
      (node (ref "P1") (pin "7") (pinfunction "PVDD_7") (pintype "passive"))
      (node (ref "R16") (pin "2") (pintype "passive"))
      (node (ref "R18") (pin "2") (pintype "passive"))
      (node (ref "R30") (pin "2") (pinfunction "2_2") (pintype "passive"))
      (node (ref "TP3") (pin "1") (pinfunction "1_1") (pintype "passive"))
      (node (ref "U5") (pin "1") (pinfunction "IN_1") (pintype "power_in"))
      (node (ref "U5") (pin "3") (pinfunction "EN_3") (pintype "input"))
    )
    (net (code "74") (name "unconnected-(P1-NRST-Pad8)") (class "Default")
      (node (ref "P1") (pin "8") (pinfunction "NRST_8") (pintype "passive"))
    )
    (net (code "75") (name "unconnected-(P1-RSV-Pad2)") (class "Default")
      (node (ref "P1") (pin "2") (pinfunction "RSV_2") (pintype "passive"))
    )
    (net (code "76") (name "unconnected-(P1-VBAT-Pad5)") (class "Default")
      (node (ref "P1") (pin "5") (pinfunction "VBAT_5") (pintype "passive"))
    )
    (net (code "77") (name "unconnected-(P2-CTS2-Pad26)") (class "Default")
      (node (ref "P2") (pin "26") (pinfunction "CTS2_26") (pintype "passive"))
    )
    (net (code "78") (name "unconnected-(P2-GND-Pad11)") (class "Default")
      (node (ref "P2") (pin "11") (pinfunction "GND_11") (pintype "passive"))
    )
    (net (code "79") (name "unconnected-(P2-GND-Pad16)") (class "Default")
      (node (ref "P2") (pin "16") (pinfunction "GND_16") (pintype "passive"))
    )
    (net (code "80") (name "unconnected-(P2-GND-Pad21)") (class "Default")
      (node (ref "P2") (pin "21") (pinfunction "GND_21") (pintype "passive"))
    )
    (net (code "81") (name "unconnected-(P2-GND-Pad24)") (class "Default")
      (node (ref "P2") (pin "24") (pinfunction "GND_24") (pintype "passive"))
    )
    (net (code "82") (name "unconnected-(P2-IO1-Pad7)") (class "Default")
      (node (ref "P2") (pin "7") (pinfunction "IO1_7") (pintype "passive"))
    )
    (net (code "83") (name "unconnected-(P2-IO2-Pad9)") (class "Default")
      (node (ref "P2") (pin "9") (pinfunction "IO2_9") (pintype "passive"))
    )
    (net (code "84") (name "unconnected-(P2-IO3-Pad14)") (class "Default")
      (node (ref "P2") (pin "14") (pinfunction "IO3_14") (pintype "passive"))
    )
    (net (code "85") (name "unconnected-(P2-IO4-Pad17)") (class "Default")
      (node (ref "P2") (pin "17") (pinfunction "IO4_17") (pintype "passive"))
    )
    (net (code "86") (name "unconnected-(P2-IO5-Pad19)") (class "Default")
      (node (ref "P2") (pin "19") (pinfunction "IO5_19") (pintype "passive"))
    )
    (net (code "87") (name "unconnected-(P2-IO6-Pad22)") (class "Default")
      (node (ref "P2") (pin "22") (pinfunction "IO6_22") (pintype "passive"))
    )
    (net (code "88") (name "unconnected-(P2-IO7-Pad31)") (class "Default")
      (node (ref "P2") (pin "31") (pinfunction "IO7_31") (pintype "passive"))
    )
    (net (code "89") (name "unconnected-(P2-PWM1-Pad23)") (class "Default")
      (node (ref "P2") (pin "23") (pinfunction "PWM1_23") (pintype "passive"))
    )
    (net (code "90") (name "unconnected-(P2-PWM2-Pad25)") (class "Default")
      (node (ref "P2") (pin "25") (pinfunction "PWM2_25") (pintype "passive"))
    )
    (net (code "91") (name "unconnected-(P2-PWM3-Pad27)") (class "Default")
      (node (ref "P2") (pin "27") (pinfunction "PWM3_27") (pintype "passive"))
    )
    (net (code "92") (name "unconnected-(P2-PWM4-Pad29)") (class "Default")
      (node (ref "P2") (pin "29") (pinfunction "PWM4_29") (pintype "passive"))
    )
    (net (code "93") (name "unconnected-(P2-RTS2-Pad28)") (class "Default")
      (node (ref "P2") (pin "28") (pinfunction "RTS2_28") (pintype "passive"))
    )
    (net (code "94") (name "unconnected-(P2-RXD1-Pad15)") (class "Default")
      (node (ref "P2") (pin "15") (pinfunction "RXD1_15") (pintype "passive"))
    )
    (net (code "95") (name "unconnected-(P2-RXD2-Pad32)") (class "Default")
      (node (ref "P2") (pin "32") (pinfunction "RXD2_32") (pintype "passive"))
    )
    (net (code "96") (name "unconnected-(P2-SCL1-Pad5)") (class "Default")
      (node (ref "P2") (pin "5") (pinfunction "SCL1_5") (pintype "passive"))
    )
    (net (code "97") (name "unconnected-(P2-SCL2-Pad20)") (class "Default")
      (node (ref "P2") (pin "20") (pinfunction "SCL2_20") (pintype "passive"))
    )
    (net (code "98") (name "unconnected-(P2-SDA1-Pad3)") (class "Default")
      (node (ref "P2") (pin "3") (pinfunction "SDA1_3") (pintype "passive"))
    )
    (net (code "99") (name "unconnected-(P2-SDA2-Pad18)") (class "Default")
      (node (ref "P2") (pin "18") (pinfunction "SDA2_18") (pintype "passive"))
    )
    (net (code "100") (name "unconnected-(P2-TXD1-Pad13)") (class "Default")
      (node (ref "P2") (pin "13") (pinfunction "TXD1_13") (pintype "passive"))
    )
    (net (code "101") (name "unconnected-(P2-TXD2-Pad30)") (class "Default")
      (node (ref "P2") (pin "30") (pinfunction "TXD2_30") (pintype "passive"))
    )
    (net (code "102") (name "unconnected-(P3-Pad1)") (class "Default")
      (node (ref "P3") (pin "1") (pinfunction "1_1") (pintype "passive"))
    )
    (net (code "103") (name "unconnected-(U3-GPIO2{slash}DCLK-Pad9)") (class "Default")
      (node (ref "U3") (pin "9") (pinfunction "GPIO2/DCLK_9") (pintype "passive"))
    )
    (net (code "104") (name "unconnected-(U3-GPIO3{slash}SDATA-Pad10)") (class "Default")
      (node (ref "U3") (pin "10") (pinfunction "GPIO3/SDATA_10") (pintype "passive"))
    )
    (net (code "105") (name "unconnected-(U3-TX-Pad27)") (class "Default")
      (node (ref "U3") (pin "27") (pinfunction "TX_27") (pintype "passive"))
    )
    (net (code "106") (name "unconnected-(U3-VCO-Pad15)") (class "Default")
      (node (ref "U3") (pin "15") (pinfunction "VCO_15") (pintype "passive"))
    )
    (net (code "107") (name "unconnected-(U4-GPIO1-Pad21)") (class "Default")
      (node (ref "U4") (pin "21") (pinfunction "GPIO1_21") (pintype "passive"))
    )
    (net (code "108") (name "unconnected-(U4-GPIO2-Pad20)") (class "Default")
      (node (ref "U4") (pin "20") (pinfunction "GPIO2_20") (pintype "passive"))
    )
    (net (code "109") (name "unconnected-(U4-GPIO3-Pad19)") (class "Default")
      (node (ref "U4") (pin "19") (pinfunction "GPIO3_19") (pintype "passive"))
    )
    (net (code "110") (name "unconnected-(U4-NC-Pad22)") (class "Default")
      (node (ref "U4") (pin "22") (pinfunction "NC_22") (pintype "passive"))
    )
    (net (code "111") (name "unconnected-(U4-NC-Pad23)") (class "Default")
      (node (ref "U4") (pin "23") (pinfunction "NC_23") (pintype "passive"))
    )
    (net (code "112") (name "unconnected-(U4-~{SEN}-Pad8)") (class "Default")
      (node (ref "U4") (pin "8") (pinfunction "~{SEN}_8") (pintype "passive"))
    )
    (net (code "113") (name "unconnected-(U5-FB-Pad4)") (class "Default")
      (node (ref "U5") (pin "4") (pinfunction "FB_4") (pintype "input+no_connect"))
    )
  )
)
